# armstrap_eagle_1_0_0.net
KiCad netlist of a schematic drawn in EAGLE
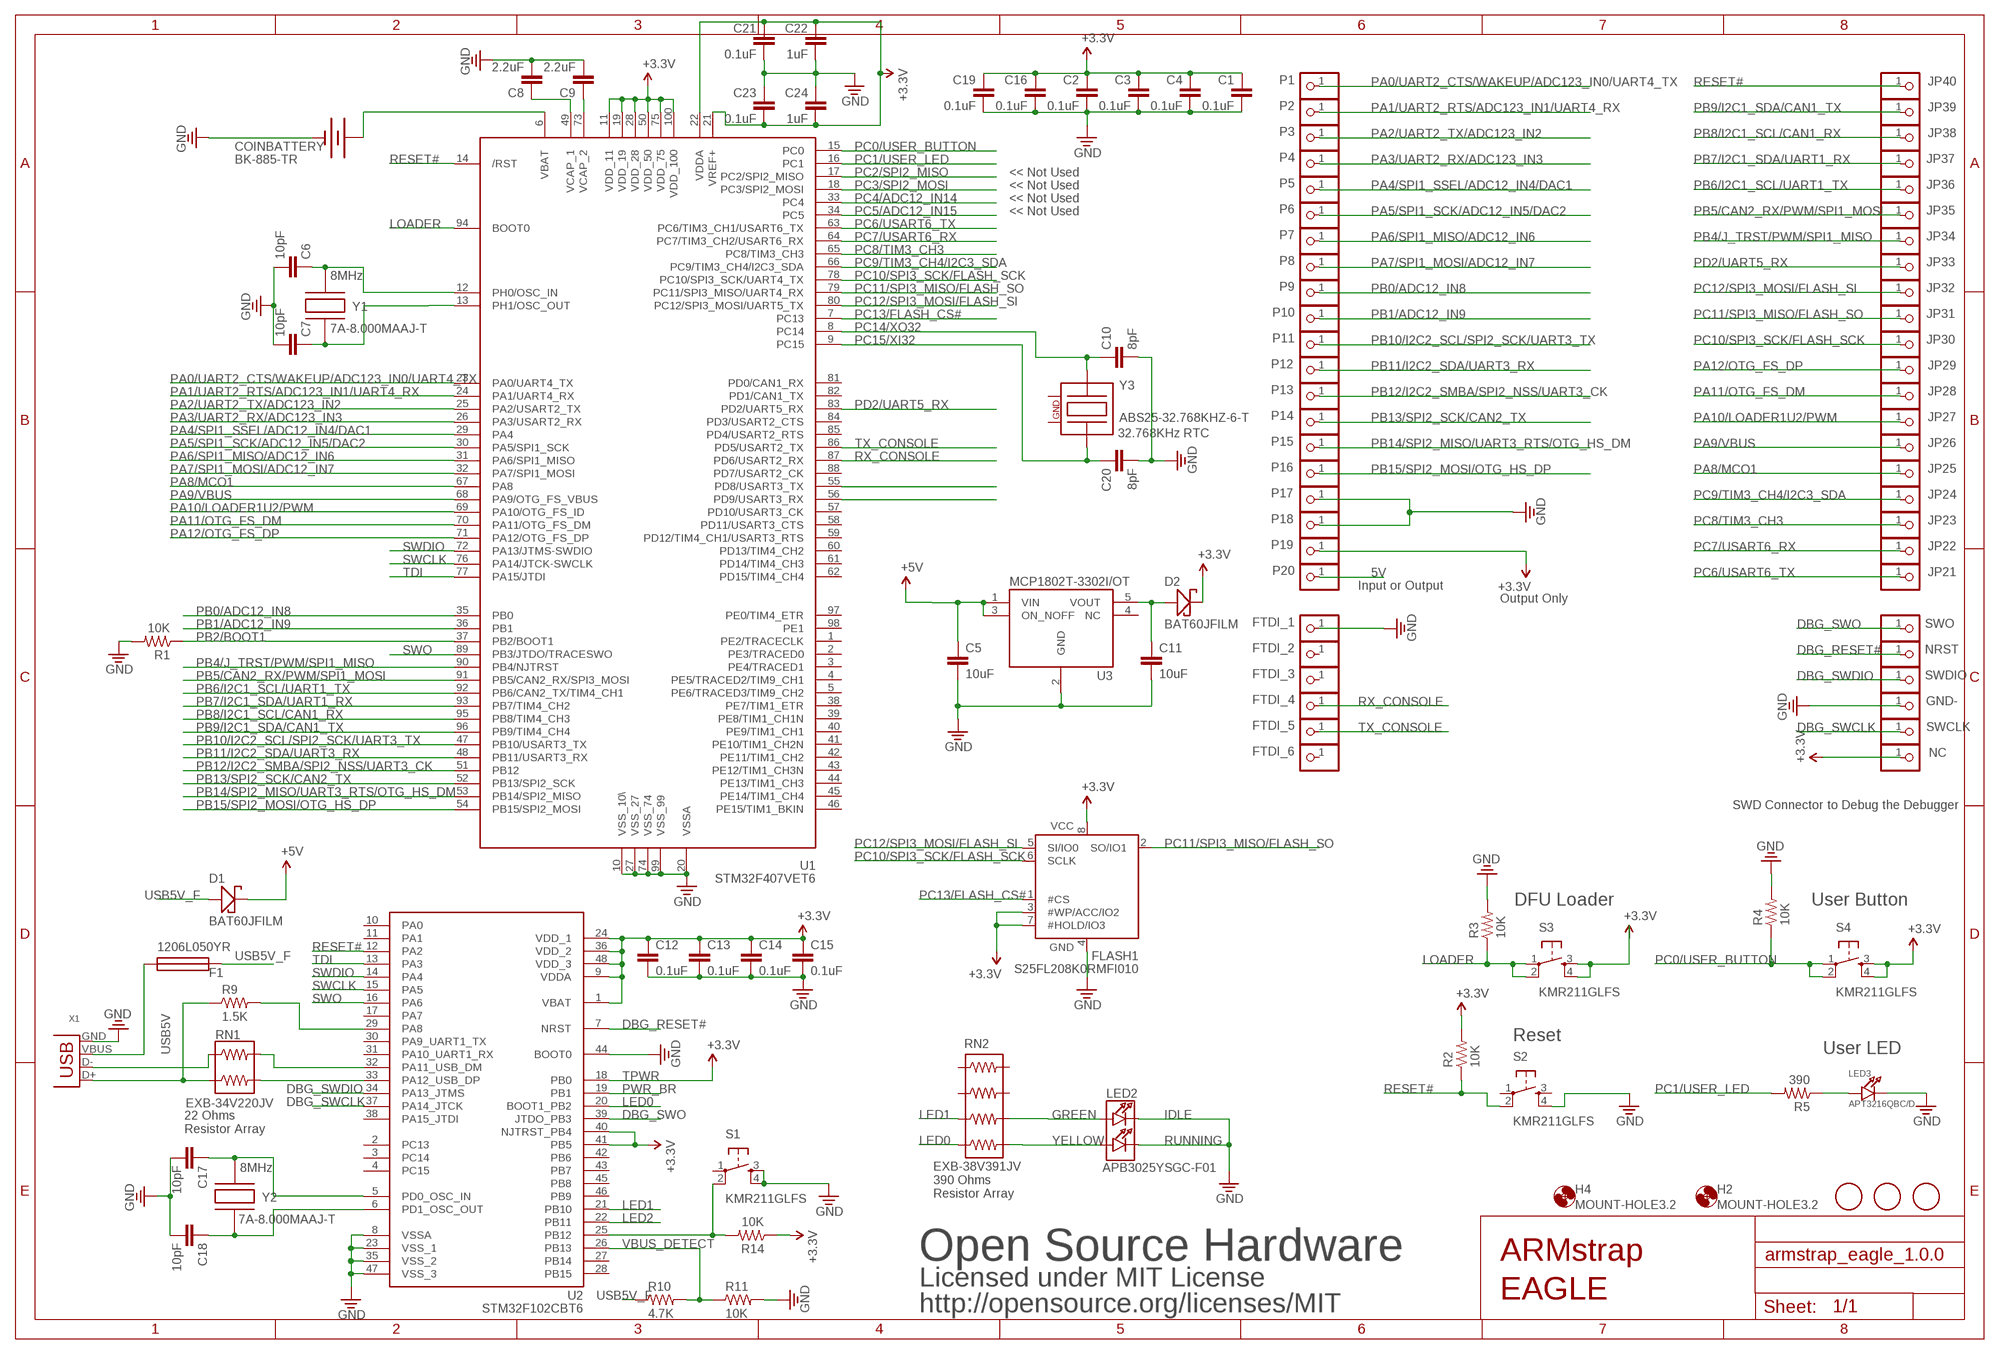
[diagram p0: schematic, sheet 1]

(export (version "E")
  (design (tool "Eeschema 10.0.6"))
  (components
    (comp (ref "C1")
      (value "0.1uF")
      (footprint "eagle-import:0805")
      (libsource (lib "eagle-import") (part "CAP0805"))
    )
    (comp (ref "C2")
      (value "0.1uF")
      (footprint "eagle-import:0805")
      (libsource (lib "eagle-import") (part "CAP0805"))
    )
    (comp (ref "C3")
      (value "0.1uF")
      (footprint "eagle-import:0805")
      (libsource (lib "eagle-import") (part "CAP0805"))
    )
    (comp (ref "C4")
      (value "0.1uF")
      (footprint "eagle-import:0805")
      (libsource (lib "eagle-import") (part "CAP0805"))
    )
    (comp (ref "C5")
      (value "10uF")
      (footprint "eagle-import:0805")
      (libsource (lib "eagle-import") (part "CAP0805"))
    )
    (comp (ref "C6")
      (value "10pF")
      (footprint "eagle-import:0805")
      (libsource (lib "eagle-import") (part "CAP0805"))
    )
    (comp (ref "C7")
      (value "10pF")
      (footprint "eagle-import:0805")
      (libsource (lib "eagle-import") (part "CAP0805"))
    )
    (comp (ref "C8")
      (value "2.2uF")
      (footprint "eagle-import:0805")
      (libsource (lib "eagle-import") (part "CAP0805"))
    )
    (comp (ref "C9")
      (value "2.2uF")
      (footprint "eagle-import:0805")
      (libsource (lib "eagle-import") (part "CAP0805"))
    )
    (comp (ref "C10")
      (value "8pF")
      (footprint "eagle-import:0805")
      (libsource (lib "eagle-import") (part "CAP0805"))
    )
    (comp (ref "C11")
      (value "10uF")
      (footprint "eagle-import:0805")
      (libsource (lib "eagle-import") (part "CAP0805"))
    )
    (comp (ref "C12")
      (value "0.1uF")
      (footprint "eagle-import:0805")
      (libsource (lib "eagle-import") (part "CAP0805"))
    )
    (comp (ref "C13")
      (value "0.1uF")
      (footprint "eagle-import:0805")
      (libsource (lib "eagle-import") (part "CAP0805"))
    )
    (comp (ref "C14")
      (value "0.1uF")
      (footprint "eagle-import:0805")
      (libsource (lib "eagle-import") (part "CAP0805"))
    )
    (comp (ref "C15")
      (value "0.1uF")
      (footprint "eagle-import:0805")
      (libsource (lib "eagle-import") (part "CAP0805"))
    )
    (comp (ref "C16")
      (value "0.1uF")
      (footprint "eagle-import:0805")
      (libsource (lib "eagle-import") (part "CAP0805"))
    )
    (comp (ref "C17")
      (value "10pF")
      (footprint "eagle-import:0805")
      (libsource (lib "eagle-import") (part "CAP0805"))
    )
    (comp (ref "C18")
      (value "10pF")
      (footprint "eagle-import:0805")
      (libsource (lib "eagle-import") (part "CAP0805"))
    )
    (comp (ref "C19")
      (value "0.1uF")
      (footprint "eagle-import:0805")
      (libsource (lib "eagle-import") (part "CAP0805"))
    )
    (comp (ref "C20")
      (value "8pF")
      (footprint "eagle-import:0805")
      (libsource (lib "eagle-import") (part "CAP0805"))
    )
    (comp (ref "C21")
      (value "0.1uF")
      (footprint "eagle-import:0805")
      (libsource (lib "eagle-import") (part "CAP0805"))
    )
    (comp (ref "C22")
      (value "1uF")
      (footprint "eagle-import:0805")
      (libsource (lib "eagle-import") (part "CAP0805"))
    )
    (comp (ref "C23")
      (value "0.1uF")
      (footprint "eagle-import:0805")
      (libsource (lib "eagle-import") (part "CAP0805"))
    )
    (comp (ref "C24")
      (value "1uF")
      (footprint "eagle-import:0805")
      (libsource (lib "eagle-import") (part "CAP0805"))
    )
    (comp (ref "COINBATTERY")
      (value "BK-885-TR")
      (footprint "eagle-import:BATTCON_12MM")
      (libsource (lib "eagle-import") (part "BATTERY12MM"))
    )
    (comp (ref "D1")
      (value "BAT60JFILM")
      (footprint "eagle-import:SOD-323")
      (libsource (lib "eagle-import") (part "SCHOTTKY"))
    )
    (comp (ref "D2")
      (value "BAT60JFILM")
      (footprint "eagle-import:SOD-323")
      (libsource (lib "eagle-import") (part "SCHOTTKY"))
    )
    (comp (ref "F1")
      (value "1206L050YR")
      (footprint "eagle-import:PTC-1206")
      (libsource (lib "eagle-import") (part "FUSE_PTC"))
    )
    (comp (ref "FID2")
      (value "FIDUCIAL")
      (footprint "eagle-import:FIDUCIAL_1MM")
      (libsource (lib "eagle-import") (part "FIDUCIAL"))
    )
    (comp (ref "FID3")
      (value "FIDUCIAL")
      (footprint "eagle-import:FIDUCIAL_1MM")
      (libsource (lib "eagle-import") (part "FIDUCIAL"))
    )
    (comp (ref "FID4")
      (value "FIDUCIAL")
      (footprint "eagle-import:FIDUCIAL_1MM")
      (libsource (lib "eagle-import") (part "FIDUCIAL"))
    )
    (comp (ref "FLASH1")
      (value "S25FL208K0RMFI010")
      (footprint "eagle-import:SOIC-8-WIDE")
      (libsource (lib "eagle-import") (part "FLASH-SPI"))
    )
    (comp (ref "FTDI_1")
      (value "PINHD-1X1")
      (footprint "eagle-import:1X01")
      (libsource (lib "eagle-import") (part "PINHD-1X1"))
    )
    (comp (ref "FTDI_2")
      (value "PINHD-1X1")
      (footprint "eagle-import:1X01")
      (libsource (lib "eagle-import") (part "PINHD-1X1"))
    )
    (comp (ref "FTDI_3")
      (value "PINHD-1X1")
      (footprint "eagle-import:1X01")
      (libsource (lib "eagle-import") (part "PINHD-1X1"))
    )
    (comp (ref "FTDI_4")
      (value "PINHD-1X1")
      (footprint "eagle-import:1X01")
      (libsource (lib "eagle-import") (part "PINHD-1X1"))
    )
    (comp (ref "FTDI_5")
      (value "PINHD-1X1")
      (footprint "eagle-import:1X01")
      (libsource (lib "eagle-import") (part "PINHD-1X1"))
    )
    (comp (ref "FTDI_6")
      (value "PINHD-1X1")
      (footprint "eagle-import:1X01")
      (libsource (lib "eagle-import") (part "PINHD-1X1"))
    )
    (comp (ref "GND-")
      (value "PINHD-1X1")
      (footprint "eagle-import:1X01")
      (libsource (lib "eagle-import") (part "PINHD-1X1"))
    )
    (comp (ref "H2")
      (value "MOUNT-HOLE3.2")
      (footprint "eagle-import:3,2")
      (libsource (lib "eagle-import") (part "MOUNT-HOLE3.2"))
    )
    (comp (ref "H4")
      (value "MOUNT-HOLE3.2")
      (footprint "eagle-import:3,2")
      (libsource (lib "eagle-import") (part "MOUNT-HOLE3.2"))
    )
    (comp (ref "JP21")
      (value "PINHD-1X1")
      (footprint "eagle-import:1X01")
      (libsource (lib "eagle-import") (part "PINHD-1X1"))
    )
    (comp (ref "JP22")
      (value "PINHD-1X1")
      (footprint "eagle-import:1X01")
      (libsource (lib "eagle-import") (part "PINHD-1X1"))
    )
    (comp (ref "JP23")
      (value "PINHD-1X1")
      (footprint "eagle-import:1X01")
      (libsource (lib "eagle-import") (part "PINHD-1X1"))
    )
    (comp (ref "JP24")
      (value "PINHD-1X1")
      (footprint "eagle-import:1X01")
      (libsource (lib "eagle-import") (part "PINHD-1X1"))
    )
    (comp (ref "JP25")
      (value "PINHD-1X1")
      (footprint "eagle-import:1X01")
      (libsource (lib "eagle-import") (part "PINHD-1X1"))
    )
    (comp (ref "JP26")
      (value "PINHD-1X1")
      (footprint "eagle-import:1X01")
      (libsource (lib "eagle-import") (part "PINHD-1X1"))
    )
    (comp (ref "JP27")
      (value "PINHD-1X1")
      (footprint "eagle-import:1X01")
      (libsource (lib "eagle-import") (part "PINHD-1X1"))
    )
    (comp (ref "JP28")
      (value "PINHD-1X1")
      (footprint "eagle-import:1X01")
      (libsource (lib "eagle-import") (part "PINHD-1X1"))
    )
    (comp (ref "JP29")
      (value "PINHD-1X1")
      (footprint "eagle-import:1X01")
      (libsource (lib "eagle-import") (part "PINHD-1X1"))
    )
    (comp (ref "JP30")
      (value "PINHD-1X1")
      (footprint "eagle-import:1X01")
      (libsource (lib "eagle-import") (part "PINHD-1X1"))
    )
    (comp (ref "JP31")
      (value "PINHD-1X1")
      (footprint "eagle-import:1X01")
      (libsource (lib "eagle-import") (part "PINHD-1X1"))
    )
    (comp (ref "JP32")
      (value "PINHD-1X1")
      (footprint "eagle-import:1X01")
      (libsource (lib "eagle-import") (part "PINHD-1X1"))
    )
    (comp (ref "JP33")
      (value "PINHD-1X1")
      (footprint "eagle-import:1X01")
      (libsource (lib "eagle-import") (part "PINHD-1X1"))
    )
    (comp (ref "JP34")
      (value "PINHD-1X1")
      (footprint "eagle-import:1X01")
      (libsource (lib "eagle-import") (part "PINHD-1X1"))
    )
    (comp (ref "JP35")
      (value "PINHD-1X1")
      (footprint "eagle-import:1X01")
      (libsource (lib "eagle-import") (part "PINHD-1X1"))
    )
    (comp (ref "JP36")
      (value "PINHD-1X1")
      (footprint "eagle-import:1X01")
      (libsource (lib "eagle-import") (part "PINHD-1X1"))
    )
    (comp (ref "JP37")
      (value "PINHD-1X1")
      (footprint "eagle-import:1X01")
      (libsource (lib "eagle-import") (part "PINHD-1X1"))
    )
    (comp (ref "JP38")
      (value "PINHD-1X1")
      (footprint "eagle-import:1X01")
      (libsource (lib "eagle-import") (part "PINHD-1X1"))
    )
    (comp (ref "JP39")
      (value "PINHD-1X1")
      (footprint "eagle-import:1X01")
      (libsource (lib "eagle-import") (part "PINHD-1X1"))
    )
    (comp (ref "JP40")
      (value "PINHD-1X1")
      (footprint "eagle-import:1X01")
      (libsource (lib "eagle-import") (part "PINHD-1X1"))
    )
    (comp (ref "LED2")
      (value "APB3025YSGC-F01")
      (footprint "eagle-import:CHIPLED_1206-DUAL")
      (libsource (lib "eagle-import") (part "LED-2"))
    )
    (comp (ref "LED3")
      (value "APT3216QBC/D")
      (footprint "eagle-import:CHIPLED_1206")
      (libsource (lib "eagle-import") (part "LED1206"))
    )
    (comp (ref "NC")
      (value "PINHD-1X1")
      (footprint "eagle-import:1X01")
      (libsource (lib "eagle-import") (part "PINHD-1X1"))
    )
    (comp (ref "NRST")
      (value "PINHD-1X1")
      (footprint "eagle-import:1X01")
      (libsource (lib "eagle-import") (part "PINHD-1X1"))
    )
    (comp (ref "P1")
      (value "PINHD-1X1")
      (footprint "eagle-import:1X01")
      (libsource (lib "eagle-import") (part "PINHD-1X1"))
    )
    (comp (ref "P2")
      (value "PINHD-1X1")
      (footprint "eagle-import:1X01")
      (libsource (lib "eagle-import") (part "PINHD-1X1"))
    )
    (comp (ref "P3")
      (value "PINHD-1X1")
      (footprint "eagle-import:1X01")
      (libsource (lib "eagle-import") (part "PINHD-1X1"))
    )
    (comp (ref "P4")
      (value "PINHD-1X1")
      (footprint "eagle-import:1X01")
      (libsource (lib "eagle-import") (part "PINHD-1X1"))
    )
    (comp (ref "P5")
      (value "PINHD-1X1")
      (footprint "eagle-import:1X01")
      (libsource (lib "eagle-import") (part "PINHD-1X1"))
    )
    (comp (ref "P6")
      (value "PINHD-1X1")
      (footprint "eagle-import:1X01")
      (libsource (lib "eagle-import") (part "PINHD-1X1"))
    )
    (comp (ref "P7")
      (value "PINHD-1X1")
      (footprint "eagle-import:1X01")
      (libsource (lib "eagle-import") (part "PINHD-1X1"))
    )
    (comp (ref "P8")
      (value "PINHD-1X1")
      (footprint "eagle-import:1X01")
      (libsource (lib "eagle-import") (part "PINHD-1X1"))
    )
    (comp (ref "P9")
      (value "PINHD-1X1")
      (footprint "eagle-import:1X01")
      (libsource (lib "eagle-import") (part "PINHD-1X1"))
    )
    (comp (ref "P10")
      (value "PINHD-1X1")
      (footprint "eagle-import:1X01")
      (libsource (lib "eagle-import") (part "PINHD-1X1"))
    )
    (comp (ref "P11")
      (value "PINHD-1X1")
      (footprint "eagle-import:1X01")
      (libsource (lib "eagle-import") (part "PINHD-1X1"))
    )
    (comp (ref "P12")
      (value "PINHD-1X1")
      (footprint "eagle-import:1X01")
      (libsource (lib "eagle-import") (part "PINHD-1X1"))
    )
    (comp (ref "P13")
      (value "PINHD-1X1")
      (footprint "eagle-import:1X01")
      (libsource (lib "eagle-import") (part "PINHD-1X1"))
    )
    (comp (ref "P14")
      (value "PINHD-1X1")
      (footprint "eagle-import:1X01")
      (libsource (lib "eagle-import") (part "PINHD-1X1"))
    )
    (comp (ref "P15")
      (value "PINHD-1X1")
      (footprint "eagle-import:1X01")
      (libsource (lib "eagle-import") (part "PINHD-1X1"))
    )
    (comp (ref "P16")
      (value "PINHD-1X1")
      (footprint "eagle-import:1X01")
      (libsource (lib "eagle-import") (part "PINHD-1X1"))
    )
    (comp (ref "P17")
      (value "PINHD-1X1")
      (footprint "eagle-import:1X01")
      (libsource (lib "eagle-import") (part "PINHD-1X1"))
    )
    (comp (ref "P18")
      (value "PINHD-1X1")
      (footprint "eagle-import:1X01")
      (libsource (lib "eagle-import") (part "PINHD-1X1"))
    )
    (comp (ref "P19")
      (value "PINHD-1X1")
      (footprint "eagle-import:1X01")
      (libsource (lib "eagle-import") (part "PINHD-1X1"))
    )
    (comp (ref "P20")
      (value "PINHD-1X1")
      (footprint "eagle-import:1X01")
      (libsource (lib "eagle-import") (part "PINHD-1X1"))
    )
    (comp (ref "R1")
      (value "10K")
      (footprint "eagle-import:0805")
      (libsource (lib "eagle-import") (part "RES0805"))
    )
    (comp (ref "R2")
      (value "10K")
      (footprint "eagle-import:0805")
      (libsource (lib "eagle-import") (part "RES0805"))
    )
    (comp (ref "R3")
      (value "10K")
      (footprint "eagle-import:0805")
      (libsource (lib "eagle-import") (part "RES0805"))
    )
    (comp (ref "R4")
      (value "10K")
      (footprint "eagle-import:0805")
      (libsource (lib "eagle-import") (part "RES0805"))
    )
    (comp (ref "R5")
      (value "390")
      (footprint "eagle-import:0805")
      (libsource (lib "eagle-import") (part "RES0805"))
    )
    (comp (ref "R9")
      (value "1.5K")
      (footprint "eagle-import:0805")
      (libsource (lib "eagle-import") (part "RES0805"))
    )
    (comp (ref "R10")
      (value "4.7K")
      (footprint "eagle-import:0805")
      (libsource (lib "eagle-import") (part "RES0805"))
    )
    (comp (ref "R11")
      (value "10K")
      (footprint "eagle-import:0805")
      (libsource (lib "eagle-import") (part "RES0805"))
    )
    (comp (ref "R14")
      (value "10K")
      (footprint "eagle-import:0805")
      (libsource (lib "eagle-import") (part "RES0805"))
    )
    (comp (ref "RN1")
      (value "EXB-34V220JV")
      (footprint "eagle-import:0603-ARC2")
      (libsource (lib "eagle-import") (part "RES-2"))
    )
    (comp (ref "RN2")
      (value "EXB-38V391JV")
      (footprint "eagle-import:0603-ARC4")
      (libsource (lib "eagle-import") (part "RES-4"))
    )
    (comp (ref "S1")
      (value "KMR211GLFS")
      (footprint "eagle-import:KMR_SWITCH")
      (libsource (lib "eagle-import") (part "TAC_SWITCH"))
    )
    (comp (ref "S2")
      (value "KMR211GLFS")
      (footprint "eagle-import:KMR_SWITCH")
      (libsource (lib "eagle-import") (part "TAC_SWITCH"))
    )
    (comp (ref "S3")
      (value "KMR211GLFS")
      (footprint "eagle-import:KMR_SWITCH")
      (libsource (lib "eagle-import") (part "TAC_SWITCH"))
    )
    (comp (ref "S4")
      (value "KMR211GLFS")
      (footprint "eagle-import:KMR_SWITCH")
      (libsource (lib "eagle-import") (part "TAC_SWITCH"))
    )
    (comp (ref "SWCLK")
      (value "PINHD-1X1")
      (footprint "eagle-import:1X01")
      (libsource (lib "eagle-import") (part "PINHD-1X1"))
    )
    (comp (ref "SWDIO")
      (value "PINHD-1X1")
      (footprint "eagle-import:1X01")
      (libsource (lib "eagle-import") (part "PINHD-1X1"))
    )
    (comp (ref "SWO")
      (value "PINHD-1X1")
      (footprint "eagle-import:1X01")
      (libsource (lib "eagle-import") (part "PINHD-1X1"))
    )
    (comp (ref "U1")
      (value "STM32F407VET6")
      (footprint "eagle-import:LQFP100")
      (libsource (lib "eagle-import") (part "STM32F407VET6"))
    )
    (comp (ref "U2")
      (value "STM32F102CBT6")
      (footprint "eagle-import:LQFP48")
      (libsource (lib "eagle-import") (part "STM32F102CBT6"))
    )
    (comp (ref "U3")
      (value "MCP1802T-3302I/OT")
      (footprint "eagle-import:MCP1802-SOT23")
      (libsource (lib "eagle-import") (part "MCP1802"))
    )
    (comp (ref "X1")
      (value "10033526-N3212MLF")
      (footprint "eagle-import:USB-MB-S")
      (libsource (lib "eagle-import") (part "USB-MB-S"))
    )
    (comp (ref "Y1")
      (value "7A-8.000MAAJ-T")
      (footprint "eagle-import:CRYSTAL-SMD-5.0MM-3.2MM-2")
      (libsource (lib "eagle-import") (part "CRYSTAL-2"))
    )
    (comp (ref "Y2")
      (value "7A-8.000MAAJ-T")
      (footprint "eagle-import:CRYSTAL-SMD-5.0MM-3.2MM-2")
      (libsource (lib "eagle-import") (part "CRYSTAL-2"))
    )
    (comp (ref "Y3")
      (value "ABS25-32.768KHZ-6-T")
      (footprint "eagle-import:CRYSTAL-SMD-32.768KHZ")
      (libsource (lib "eagle-import") (part "CRYSTAL"))
    )
  )
  (nets
    (net (code "1") (name "+3.3V") (class "Default")
      (node (ref "C1") (pin "1") (pinfunction "1_1") (pintype "passive"))
      (node (ref "C12") (pin "1") (pinfunction "1_1") (pintype "passive"))
      (node (ref "C13") (pin "1") (pinfunction "1_1") (pintype "passive"))
      (node (ref "C14") (pin "1") (pinfunction "1_1") (pintype "passive"))
      (node (ref "C15") (pin "1") (pinfunction "1_1") (pintype "passive"))
      (node (ref "C16") (pin "1") (pinfunction "1_1") (pintype "passive"))
      (node (ref "C19") (pin "1") (pinfunction "1_1") (pintype "passive"))
      (node (ref "C2") (pin "1") (pinfunction "1_1") (pintype "passive"))
      (node (ref "C21") (pin "1") (pinfunction "1_1") (pintype "passive"))
      (node (ref "C22") (pin "1") (pinfunction "1_1") (pintype "passive"))
      (node (ref "C23") (pin "2") (pinfunction "2_2") (pintype "passive"))
      (node (ref "C24") (pin "2") (pinfunction "2_2") (pintype "passive"))
      (node (ref "C3") (pin "1") (pinfunction "1_1") (pintype "passive"))
      (node (ref "C4") (pin "1") (pinfunction "1_1") (pintype "passive"))
      (node (ref "D2") (pin "CATHODE") (pinfunction "C_CATHODE") (pintype "power_in"))
      (node (ref "FLASH1") (pin "3") (pinfunction "#WP/ACC/IO2_3") (pintype "bidirectional"))
      (node (ref "FLASH1") (pin "7") (pinfunction "#HOLD/IO3_7") (pintype "bidirectional"))
      (node (ref "FLASH1") (pin "8") (pinfunction "VCC_8") (pintype "power_in"))
      (node (ref "NC") (pin "1") (pinfunction "1_1") (pintype "passive"))
      (node (ref "P19") (pin "1") (pinfunction "1_1") (pintype "passive"))
      (node (ref "R14") (pin "1") (pinfunction "1_1") (pintype "passive"))
      (node (ref "R2") (pin "2") (pinfunction "2_2") (pintype "passive"))
      (node (ref "S3") (pin "3") (pinfunction "3_3") (pintype "passive"))
      (node (ref "S3") (pin "4") (pinfunction "4_4") (pintype "passive"))
      (node (ref "S4") (pin "3") (pinfunction "3_3") (pintype "passive"))
      (node (ref "S4") (pin "4") (pinfunction "4_4") (pintype "passive"))
      (node (ref "U1") (pin "100") (pinfunction "VDD_100_100") (pintype "power_in"))
      (node (ref "U1") (pin "11") (pinfunction "VDD_11_11") (pintype "power_in"))
      (node (ref "U1") (pin "19") (pinfunction "VDD_19_19") (pintype "power_in"))
      (node (ref "U1") (pin "21") (pinfunction "VREF+_21") (pintype "power_in"))
      (node (ref "U1") (pin "22") (pinfunction "VDDA_22") (pintype "power_in"))
      (node (ref "U1") (pin "28") (pinfunction "VDD_28_28") (pintype "power_in"))
      (node (ref "U1") (pin "50") (pinfunction "VDD_50_50") (pintype "power_in"))
      (node (ref "U1") (pin "75") (pinfunction "VDD_75_75") (pintype "power_in"))
      (node (ref "U2") (pin "1") (pinfunction "VBAT_1") (pintype "power_in"))
      (node (ref "U2") (pin "18") (pinfunction "PB0_18") (pintype "bidirectional"))
      (node (ref "U2") (pin "24") (pinfunction "VDD_1_24") (pintype "power_in"))
      (node (ref "U2") (pin "36") (pinfunction "VDD_2_36") (pintype "power_in"))
      (node (ref "U2") (pin "40") (pinfunction "NJTRST_PB4_40") (pintype "bidirectional"))
      (node (ref "U2") (pin "41") (pinfunction "PB5_41") (pintype "bidirectional"))
      (node (ref "U2") (pin "48") (pinfunction "VDD_3_48") (pintype "power_in"))
      (node (ref "U2") (pin "9") (pinfunction "VDDA_9") (pintype "power_in"))
    )
    (net (code "2") (name "+5V") (class "Default")
      (node (ref "C5") (pin "1") (pinfunction "1_1") (pintype "passive"))
      (node (ref "D1") (pin "CATHODE") (pinfunction "C_CATHODE") (pintype "power_in"))
      (node (ref "P20") (pin "1") (pinfunction "1_1") (pintype "passive"))
      (node (ref "U3") (pin "1") (pinfunction "VIN_1") (pintype "power_in"))
      (node (ref "U3") (pin "3") (pinfunction "ON_NOFF_3") (pintype "bidirectional"))
    )
    (net (code "3") (name "/2") (class "Default")
      (node (ref "Y3") (pin "2") (pinfunction "2_2") (pintype "power_in"))
    )
    (net (code "4") (name "/4") (class "Default")
      (node (ref "Y3") (pin "3") (pinfunction "4_3") (pintype "power_in"))
    )
    (net (code "5") (name "/DBG_RESET#") (class "Default")
      (node (ref "NRST") (pin "1") (pinfunction "1_1") (pintype "passive"))
      (node (ref "U2") (pin "7") (pinfunction "NRST_7") (pintype "bidirectional"))
    )
    (net (code "6") (name "/DBG_SWCLK") (class "Default")
      (node (ref "SWCLK") (pin "1") (pinfunction "1_1") (pintype "passive"))
      (node (ref "U2") (pin "37") (pinfunction "PA14_JTCK_37") (pintype "bidirectional"))
    )
    (net (code "7") (name "/DBG_SWDIO") (class "Default")
      (node (ref "SWDIO") (pin "1") (pinfunction "1_1") (pintype "passive"))
      (node (ref "U2") (pin "34") (pinfunction "PA13_JTMS_34") (pintype "bidirectional"))
    )
    (net (code "8") (name "/DBG_SWO") (class "Default")
      (node (ref "SWO") (pin "1") (pinfunction "1_1") (pintype "passive"))
      (node (ref "U2") (pin "39") (pinfunction "JTDO_PB3_39") (pintype "bidirectional"))
    )
    (net (code "9") (name "/LED0") (class "Default")
      (node (ref "RN2") (pin "4") (pinfunction "4_4") (pintype "passive"))
      (node (ref "U2") (pin "20") (pinfunction "BOOT1_PB2_20") (pintype "bidirectional"))
    )
    (net (code "10") (name "/LED1") (class "Default")
      (node (ref "RN2") (pin "3") (pinfunction "3_3") (pintype "passive"))
      (node (ref "U2") (pin "21") (pinfunction "PB10_21") (pintype "bidirectional"))
    )
    (net (code "11") (name "/LED2") (class "Default")
      (node (ref "U2") (pin "22") (pinfunction "PB11_22") (pintype "bidirectional"))
    )
    (net (code "12") (name "/LOADER") (class "Default")
      (node (ref "R3") (pin "1") (pinfunction "1_1") (pintype "passive"))
      (node (ref "S3") (pin "1") (pinfunction "1_1") (pintype "passive"))
      (node (ref "S3") (pin "2") (pinfunction "2_2") (pintype "passive"))
      (node (ref "U1") (pin "94") (pinfunction "BOOT0_94") (pintype "bidirectional"))
    )
    (net (code "13") (name "/PA0{slash}UART2_CTS{slash}WAKEUP{slash}ADC123_IN0{slash}UART4_TX") (class "Default")
      (node (ref "P1") (pin "1") (pinfunction "1_1") (pintype "passive"))
      (node (ref "U1") (pin "23") (pinfunction "PA0/UART4_TX_23") (pintype "bidirectional"))
    )
    (net (code "14") (name "/PA1{slash}UART2_RTS{slash}ADC123_IN1{slash}UART4_RX") (class "Default")
      (node (ref "P2") (pin "1") (pinfunction "1_1") (pintype "passive"))
      (node (ref "U1") (pin "24") (pinfunction "PA1/UART4_RX_24") (pintype "bidirectional"))
    )
    (net (code "15") (name "/PA2{slash}UART2_TX{slash}ADC123_IN2") (class "Default")
      (node (ref "P3") (pin "1") (pinfunction "1_1") (pintype "passive"))
      (node (ref "U1") (pin "25") (pinfunction "PA2/USART2_TX_25") (pintype "bidirectional"))
    )
    (net (code "16") (name "/PA3{slash}UART2_RX{slash}ADC123_IN3") (class "Default")
      (node (ref "P4") (pin "1") (pinfunction "1_1") (pintype "passive"))
      (node (ref "U1") (pin "26") (pinfunction "PA3/USART2_RX_26") (pintype "bidirectional"))
    )
    (net (code "17") (name "/PA4{slash}SPI1_SSEL{slash}ADC12_IN4{slash}DAC1") (class "Default")
      (node (ref "P5") (pin "1") (pinfunction "1_1") (pintype "passive"))
      (node (ref "U1") (pin "29") (pinfunction "PA4_29") (pintype "bidirectional"))
    )
    (net (code "18") (name "/PA5{slash}SPI1_SCK{slash}ADC12_IN5{slash}DAC2") (class "Default")
      (node (ref "P6") (pin "1") (pinfunction "1_1") (pintype "passive"))
      (node (ref "U1") (pin "30") (pinfunction "PA5/SPI1_SCK_30") (pintype "bidirectional"))
    )
    (net (code "19") (name "/PA6{slash}SPI1_MISO{slash}ADC12_IN6") (class "Default")
      (node (ref "P7") (pin "1") (pinfunction "1_1") (pintype "passive"))
      (node (ref "U1") (pin "31") (pinfunction "PA6/SPI1_MISO_31") (pintype "bidirectional"))
    )
    (net (code "20") (name "/PA7{slash}SPI1_MOSI{slash}ADC12_IN7") (class "Default")
      (node (ref "P8") (pin "1") (pinfunction "1_1") (pintype "passive"))
      (node (ref "U1") (pin "32") (pinfunction "PA7/SPI1_MOSI_32") (pintype "bidirectional"))
    )
    (net (code "21") (name "/PA8{slash}MCO1") (class "Default")
      (node (ref "JP25") (pin "1") (pinfunction "1_1") (pintype "passive"))
      (node (ref "U1") (pin "67") (pinfunction "PA8_67") (pintype "bidirectional"))
    )
    (net (code "22") (name "/PA9{slash}VBUS") (class "Default")
      (node (ref "JP26") (pin "1") (pinfunction "1_1") (pintype "passive"))
      (node (ref "U1") (pin "68") (pinfunction "PA9/OTG_FS_VBUS_68") (pintype "bidirectional"))
    )
    (net (code "23") (name "/PA10{slash}LOADER1U2{slash}PWM") (class "Default")
      (node (ref "JP27") (pin "1") (pinfunction "1_1") (pintype "passive"))
      (node (ref "U1") (pin "69") (pinfunction "PA10/OTG_FS_ID_69") (pintype "bidirectional"))
    )
    (net (code "24") (name "/PA11{slash}OTG_FS_DM") (class "Default")
      (node (ref "JP28") (pin "1") (pinfunction "1_1") (pintype "passive"))
      (node (ref "U1") (pin "70") (pinfunction "PA11/OTG_FS_DM_70") (pintype "bidirectional"))
    )
    (net (code "25") (name "/PA12{slash}OTG_FS_DP") (class "Default")
      (node (ref "JP29") (pin "1") (pinfunction "1_1") (pintype "passive"))
      (node (ref "U1") (pin "71") (pinfunction "PA12/OTG_FS_DP_71") (pintype "bidirectional"))
    )
    (net (code "26") (name "/PB0{slash}ADC12_IN8") (class "Default")
      (node (ref "P9") (pin "1") (pinfunction "1_1") (pintype "passive"))
      (node (ref "U1") (pin "35") (pinfunction "PB0_35") (pintype "bidirectional"))
    )
    (net (code "27") (name "/PB1{slash}ADC12_IN9") (class "Default")
      (node (ref "P10") (pin "1") (pinfunction "1_1") (pintype "passive"))
      (node (ref "U1") (pin "36") (pinfunction "PB1_36") (pintype "bidirectional"))
    )
    (net (code "28") (name "/PB2{slash}BOOT1") (class "Default")
      (node (ref "R1") (pin "1") (pinfunction "1_1") (pintype "passive"))
      (node (ref "U1") (pin "37") (pinfunction "PB2/BOOT1_37") (pintype "bidirectional"))
    )
    (net (code "29") (name "/PB4{slash}J_TRST{slash}PWM{slash}SPI1_MISO") (class "Default")
      (node (ref "JP34") (pin "1") (pinfunction "1_1") (pintype "passive"))
      (node (ref "U1") (pin "90") (pinfunction "PB4/NJTRST_90") (pintype "bidirectional"))
    )
    (net (code "30") (name "/PB5{slash}CAN2_RX{slash}PWM{slash}SPI1_MOSI") (class "Default")
      (node (ref "JP35") (pin "1") (pinfunction "1_1") (pintype "passive"))
      (node (ref "U1") (pin "91") (pinfunction "PB5/CAN2_RX/SPI3_MOSI_91") (pintype "bidirectional"))
    )
    (net (code "31") (name "/PB6{slash}I2C1_SCL{slash}UART1_TX") (class "Default")
      (node (ref "JP36") (pin "1") (pinfunction "1_1") (pintype "passive"))
      (node (ref "U1") (pin "92") (pinfunction "PB6/CAN2_TX/TIM4_CH1_92") (pintype "bidirectional"))
    )
    (net (code "32") (name "/PB7{slash}I2C1_SDA{slash}UART1_RX") (class "Default")
      (node (ref "JP37") (pin "1") (pinfunction "1_1") (pintype "passive"))
      (node (ref "U1") (pin "93") (pinfunction "PB7/TIM4_CH2_93") (pintype "bidirectional"))
    )
    (net (code "33") (name "/PB8{slash}I2C1_SCL{slash}CAN1_RX") (class "Default")
      (node (ref "JP38") (pin "1") (pinfunction "1_1") (pintype "passive"))
      (node (ref "U1") (pin "95") (pinfunction "PB8/TIM4_CH3_95") (pintype "bidirectional"))
    )
    (net (code "34") (name "/PB9{slash}I2C1_SDA{slash}CAN1_TX") (class "Default")
      (node (ref "JP39") (pin "1") (pinfunction "1_1") (pintype "passive"))
      (node (ref "U1") (pin "96") (pinfunction "PB9/TIM4_CH4_96") (pintype "bidirectional"))
    )
    (net (code "35") (name "/PB10{slash}I2C2_SCL{slash}SPI2_SCK{slash}UART3_TX") (class "Default")
      (node (ref "P11") (pin "1") (pinfunction "1_1") (pintype "passive"))
      (node (ref "U1") (pin "47") (pinfunction "PB10/USART3_TX_47") (pintype "bidirectional"))
    )
    (net (code "36") (name "/PB11{slash}I2C2_SDA{slash}UART3_RX") (class "Default")
      (node (ref "P12") (pin "1") (pinfunction "1_1") (pintype "passive"))
      (node (ref "U1") (pin "48") (pinfunction "PB11/USART3_RX_48") (pintype "bidirectional"))
    )
    (net (code "37") (name "/PB12{slash}I2C2_SMBA{slash}SPI2_NSS{slash}UART3_CK") (class "Default")
      (node (ref "P13") (pin "1") (pinfunction "1_1") (pintype "passive"))
      (node (ref "U1") (pin "51") (pinfunction "PB12_51") (pintype "bidirectional"))
    )
    (net (code "38") (name "/PB13{slash}SPI2_SCK{slash}CAN2_TX") (class "Default")
      (node (ref "P14") (pin "1") (pinfunction "1_1") (pintype "passive"))
      (node (ref "U1") (pin "52") (pinfunction "PB13/SPI2_SCK_52") (pintype "bidirectional"))
    )
    (net (code "39") (name "/PB14{slash}SPI2_MISO{slash}UART3_RTS{slash}OTG_HS_DM") (class "Default")
      (node (ref "P15") (pin "1") (pinfunction "1_1") (pintype "passive"))
      (node (ref "U1") (pin "53") (pinfunction "PB14/SPI2_MISO_53") (pintype "bidirectional"))
    )
    (net (code "40") (name "/PB15{slash}SPI2_MOSI{slash}OTG_HS_DP") (class "Default")
      (node (ref "P16") (pin "1") (pinfunction "1_1") (pintype "passive"))
      (node (ref "U1") (pin "54") (pinfunction "PB15/SPI2_MOSI_54") (pintype "bidirectional"))
    )
    (net (code "41") (name "/PC0{slash}USER_BUTTON") (class "Default")
      (node (ref "R4") (pin "1") (pinfunction "1_1") (pintype "passive"))
      (node (ref "S4") (pin "1") (pinfunction "1_1") (pintype "passive"))
      (node (ref "S4") (pin "2") (pinfunction "2_2") (pintype "passive"))
      (node (ref "U1") (pin "15") (pinfunction "PC0_15") (pintype "bidirectional"))
    )
    (net (code "42") (name "/PC1{slash}USER_LED") (class "Default")
      (node (ref "R5") (pin "2") (pinfunction "2_2") (pintype "passive"))
      (node (ref "U1") (pin "16") (pinfunction "PC1_16") (pintype "bidirectional"))
    )
    (net (code "43") (name "/PC2{slash}SPI2_MISO") (class "Default")
      (node (ref "U1") (pin "17") (pinfunction "PC2/SPI2_MISO_17") (pintype "bidirectional"))
    )
    (net (code "44") (name "/PC3{slash}SPI2_MOSI") (class "Default")
      (node (ref "U1") (pin "18") (pinfunction "PC3/SPI2_MOSI_18") (pintype "bidirectional"))
    )
    (net (code "45") (name "/PC4{slash}ADC12_IN14") (class "Default")
      (node (ref "U1") (pin "33") (pinfunction "PC4_33") (pintype "bidirectional"))
    )
    (net (code "46") (name "/PC5{slash}ADC12_IN15") (class "Default")
      (node (ref "U1") (pin "34") (pinfunction "PC5_34") (pintype "bidirectional"))
    )
    (net (code "47") (name "/PC6{slash}USART6_TX") (class "Default")
      (node (ref "JP21") (pin "1") (pinfunction "1_1") (pintype "passive"))
      (node (ref "U1") (pin "63") (pinfunction "PC6/TIM3_CH1/USART6_TX_63") (pintype "bidirectional"))
    )
    (net (code "48") (name "/PC7{slash}USART6_RX") (class "Default")
      (node (ref "JP22") (pin "1") (pinfunction "1_1") (pintype "passive"))
      (node (ref "U1") (pin "64") (pinfunction "PC7/TIM3_CH2/USART6_RX_64") (pintype "bidirectional"))
    )
    (net (code "49") (name "/PC8{slash}TIM3_CH3") (class "Default")
      (node (ref "JP23") (pin "1") (pinfunction "1_1") (pintype "passive"))
      (node (ref "U1") (pin "65") (pinfunction "PC8/TIM3_CH3_65") (pintype "bidirectional"))
    )
    (net (code "50") (name "/PC9{slash}TIM3_CH4{slash}I2C3_SDA") (class "Default")
      (node (ref "JP24") (pin "1") (pinfunction "1_1") (pintype "passive"))
      (node (ref "U1") (pin "66") (pinfunction "PC9/TIM3_CH4/I2C3_SDA_66") (pintype "bidirectional"))
    )
    (net (code "51") (name "/PC10{slash}SPI3_SCK{slash}FLASH_SCK") (class "Default")
      (node (ref "FLASH1") (pin "6") (pinfunction "SCLK_6") (pintype "bidirectional"))
      (node (ref "JP30") (pin "1") (pinfunction "1_1") (pintype "passive"))
      (node (ref "U1") (pin "78") (pinfunction "PC10/SPI3_SCK/UART4_TX_78") (pintype "bidirectional"))
    )
    (net (code "52") (name "/PC11{slash}SPI3_MISO{slash}FLASH_SO") (class "Default")
      (node (ref "FLASH1") (pin "2") (pinfunction "SO/IO1_2") (pintype "bidirectional"))
      (node (ref "JP31") (pin "1") (pinfunction "1_1") (pintype "passive"))
      (node (ref "U1") (pin "79") (pinfunction "PC11/SPI3_MISO/UART4_RX_79") (pintype "bidirectional"))
    )
    (net (code "53") (name "/PC12{slash}SPI3_MOSI{slash}FLASH_SI") (class "Default")
      (node (ref "FLASH1") (pin "5") (pinfunction "SI/IO0_5") (pintype "bidirectional"))
      (node (ref "JP32") (pin "1") (pinfunction "1_1") (pintype "passive"))
      (node (ref "U1") (pin "80") (pinfunction "PC12/SPI3_MOSI/UART5_TX_80") (pintype "bidirectional"))
    )
    (net (code "54") (name "/PC13{slash}FLASH_CS#") (class "Default")
      (node (ref "FLASH1") (pin "1") (pinfunction "#CS_1") (pintype "bidirectional"))
      (node (ref "U1") (pin "7") (pinfunction "PC13_7") (pintype "bidirectional"))
    )
    (net (code "55") (name "/PC14{slash}XO32") (class "Default")
      (node (ref "C10") (pin "1") (pinfunction "1_1") (pintype "passive"))
      (node (ref "U1") (pin "8") (pinfunction "PC14_8") (pintype "bidirectional"))
      (node (ref "Y3") (pin "1") (pinfunction "1_1") (pintype "bidirectional"))
    )
    (net (code "56") (name "/PC15{slash}XI32") (class "Default")
      (node (ref "C20") (pin "1") (pinfunction "1_1") (pintype "passive"))
      (node (ref "U1") (pin "9") (pinfunction "PC15_9") (pintype "bidirectional"))
      (node (ref "Y3") (pin "4") (pinfunction "3_4") (pintype "bidirectional"))
    )
    (net (code "57") (name "/PD2{slash}UART5_RX") (class "Default")
      (node (ref "JP33") (pin "1") (pinfunction "1_1") (pintype "passive"))
      (node (ref "U1") (pin "83") (pinfunction "PD2/UART5_RX_83") (pintype "bidirectional"))
    )
    (net (code "58") (name "/PWR_BR") (class "Default")
      (node (ref "U2") (pin "19") (pinfunction "PB1_19") (pintype "bidirectional"))
    )
    (net (code "59") (name "/RESET#") (class "Default")
      (node (ref "JP40") (pin "1") (pinfunction "1_1") (pintype "passive"))
      (node (ref "R2") (pin "1") (pinfunction "1_1") (pintype "passive"))
      (node (ref "S2") (pin "2") (pinfunction "2_2") (pintype "passive"))
      (node (ref "U1") (pin "14") (pinfunction "/RST_14") (pintype "bidirectional"))
      (node (ref "U2") (pin "12") (pinfunction "PA2_12") (pintype "bidirectional"))
    )
    (net (code "60") (name "/RX_CONSOLE") (class "Default")
      (node (ref "FTDI_4") (pin "1") (pinfunction "1_1") (pintype "passive"))
      (node (ref "U1") (pin "87") (pinfunction "PD6/USART2_RX_87") (pintype "bidirectional"))
    )
    (net (code "61") (name "/SWCLK") (class "Default")
      (node (ref "U1") (pin "76") (pinfunction "PA14/JTCK-SWCLK_76") (pintype "bidirectional"))
      (node (ref "U2") (pin "15") (pinfunction "PA5_15") (pintype "bidirectional"))
    )
    (net (code "62") (name "/SWDIO") (class "Default")
      (node (ref "U1") (pin "72") (pinfunction "PA13/JTMS-SWDIO_72") (pintype "bidirectional"))
      (node (ref "U2") (pin "14") (pinfunction "PA4_14") (pintype "bidirectional"))
    )
    (net (code "63") (name "/SWO") (class "Default")
      (node (ref "U1") (pin "89") (pinfunction "PB3/JTDO/TRACESWO_89") (pintype "bidirectional"))
      (node (ref "U2") (pin "16") (pinfunction "PA6_16") (pintype "bidirectional"))
    )
    (net (code "64") (name "/TDI") (class "Default")
      (node (ref "U1") (pin "77") (pinfunction "PA15/JTDI_77") (pintype "bidirectional"))
      (node (ref "U2") (pin "13") (pinfunction "PA3_13") (pintype "bidirectional"))
    )
    (net (code "65") (name "/TX_CONSOLE") (class "Default")
      (node (ref "FTDI_5") (pin "1") (pinfunction "1_1") (pintype "passive"))
      (node (ref "U1") (pin "86") (pinfunction "PD5/USART2_TX_86") (pintype "bidirectional"))
    )
    (net (code "66") (name "/USB5V") (class "Default")
      (node (ref "F1") (pin "1") (pinfunction "1_1") (pintype "bidirectional"))
      (node (ref "X1") (pin "VBUS") (pinfunction "VBUS_VBUS") (pintype "bidirectional"))
    )
    (net (code "67") (name "/USB5V_F") (class "Default")
      (node (ref "D1") (pin "ANODE") (pinfunction "A_ANODE") (pintype "power_in"))
      (node (ref "F1") (pin "2") (pinfunction "2_2") (pintype "bidirectional"))
      (node (ref "R10") (pin "1") (pinfunction "1_1") (pintype "passive"))
    )
    (net (code "68") (name "/VBUS_DETECT") (class "Default")
      (node (ref "R10") (pin "2") (pinfunction "2_2") (pintype "passive"))
      (node (ref "R11") (pin "1") (pinfunction "1_1") (pintype "passive"))
      (node (ref "U2") (pin "26") (pinfunction "PB13_26") (pintype "bidirectional"))
    )
    (net (code "69") (name "GND") (class "Default")
      (node (ref "C1") (pin "2") (pinfunction "2_2") (pintype "passive"))
      (node (ref "C10") (pin "2") (pinfunction "2_2") (pintype "passive"))
      (node (ref "C11") (pin "2") (pinfunction "2_2") (pintype "passive"))
      (node (ref "C12") (pin "2") (pinfunction "2_2") (pintype "passive"))
      (node (ref "C13") (pin "2") (pinfunction "2_2") (pintype "passive"))
      (node (ref "C14") (pin "2") (pinfunction "2_2") (pintype "passive"))
      (node (ref "C15") (pin "2") (pinfunction "2_2") (pintype "passive"))
      (node (ref "C16") (pin "2") (pinfunction "2_2") (pintype "passive"))
      (node (ref "C17") (pin "2") (pinfunction "2_2") (pintype "passive"))
      (node (ref "C18") (pin "2") (pinfunction "2_2") (pintype "passive"))
      (node (ref "C19") (pin "2") (pinfunction "2_2") (pintype "passive"))
      (node (ref "C2") (pin "2") (pinfunction "2_2") (pintype "passive"))
      (node (ref "C20") (pin "2") (pinfunction "2_2") (pintype "passive"))
      (node (ref "C21") (pin "2") (pinfunction "2_2") (pintype "passive"))
      (node (ref "C22") (pin "2") (pinfunction "2_2") (pintype "passive"))
      (node (ref "C23") (pin "1") (pinfunction "1_1") (pintype "passive"))
      (node (ref "C24") (pin "1") (pinfunction "1_1") (pintype "passive"))
      (node (ref "C3") (pin "2") (pinfunction "2_2") (pintype "passive"))
      (node (ref "C4") (pin "2") (pinfunction "2_2") (pintype "passive"))
      (node (ref "C5") (pin "2") (pinfunction "2_2") (pintype "passive"))
      (node (ref "C6") (pin "2") (pinfunction "2_2") (pintype "passive"))
      (node (ref "C7") (pin "2") (pinfunction "2_2") (pintype "passive"))
      (node (ref "C8") (pin "2") (pinfunction "2_2") (pintype "passive"))
      (node (ref "C9") (pin "2") (pinfunction "2_2") (pintype "passive"))
      (node (ref "COINBATTERY") (pin "GND") (pinfunction "-_GND") (pintype "power_in"))
      (node (ref "FLASH1") (pin "4") (pinfunction "GND_4") (pintype "power_in"))
      (node (ref "FTDI_1") (pin "1") (pinfunction "1_1") (pintype "passive"))
      (node (ref "GND-") (pin "1") (pinfunction "1_1") (pintype "passive"))
      (node (ref "LED2") (pin "2") (pinfunction "2_2") (pintype "passive"))
      (node (ref "LED2") (pin "4") (pinfunction "4_4") (pintype "passive"))
      (node (ref "LED3") (pin "C") (pinfunction "C_C") (pintype "passive"))
      (node (ref "P17") (pin "1") (pinfunction "1_1") (pintype "passive"))
      (node (ref "P18") (pin "1") (pinfunction "1_1") (pintype "passive"))
      (node (ref "R1") (pin "2") (pinfunction "2_2") (pintype "passive"))
      (node (ref "R11") (pin "2") (pinfunction "2_2") (pintype "passive"))
      (node (ref "R3") (pin "2") (pinfunction "2_2") (pintype "passive"))
      (node (ref "R4") (pin "2") (pinfunction "2_2") (pintype "passive"))
      (node (ref "S1") (pin "3") (pinfunction "3_3") (pintype "passive"))
      (node (ref "S1") (pin "4") (pinfunction "4_4") (pintype "passive"))
      (node (ref "S2") (pin "4") (pinfunction "4_4") (pintype "passive"))
      (node (ref "U1") (pin "10") (pinfunction "VSS_10\\_10") (pintype "power_in"))
      (node (ref "U1") (pin "20") (pinfunction "VSSA_20") (pintype "power_in"))
      (node (ref "U1") (pin "27") (pinfunction "VSS_27_27") (pintype "power_in"))
      (node (ref "U1") (pin "74") (pinfunction "VSS_74_74") (pintype "power_in"))
      (node (ref "U1") (pin "99") (pinfunction "VSS_99_99") (pintype "power_in"))
      (node (ref "U2") (pin "23") (pinfunction "VSS_1_23") (pintype "power_in"))
      (node (ref "U2") (pin "35") (pinfunction "VSS_2_35") (pintype "power_in"))
      (node (ref "U2") (pin "44") (pinfunction "BOOT0_44") (pintype "bidirectional"))
      (node (ref "U2") (pin "47") (pinfunction "VSS_3_47") (pintype "power_in"))
      (node (ref "U2") (pin "8") (pinfunction "VSSA_8") (pintype "power_in"))
      (node (ref "U3") (pin "2") (pinfunction "GND_2") (pintype "power_in"))
      (node (ref "X1") (pin "GND") (pinfunction "GND_GND") (pintype "bidirectional"))
    )
    (net (code "70") (name "Net-(COINBATTERY-+)") (class "Default")
      (node (ref "COINBATTERY") (pin "PWR@2") (pinfunction "+_PWR@2") (pintype "power_in"))
      (node (ref "U1") (pin "6") (pinfunction "VBAT_6") (pintype "power_in"))
    )
    (net (code "71") (name "Net-(D2-A)") (class "Default")
      (node (ref "C11") (pin "1") (pinfunction "1_1") (pintype "passive"))
      (node (ref "D2") (pin "ANODE") (pinfunction "A_ANODE") (pintype "power_in"))
      (node (ref "U3") (pin "5") (pinfunction "VOUT_5") (pintype "power_in"))
    )
    (net (code "72") (name "Net-(LED2-Pad1)") (class "Default")
      (node (ref "LED2") (pin "1") (pinfunction "1_1") (pintype "passive"))
      (node (ref "RN2") (pin "5") (pinfunction "5_5") (pintype "passive"))
    )
    (net (code "73") (name "Net-(LED2-Pad3)") (class "Default")
      (node (ref "LED2") (pin "3") (pinfunction "3_3") (pintype "passive"))
      (node (ref "RN2") (pin "6") (pinfunction "6_6") (pintype "passive"))
    )
    (net (code "74") (name "Net-(LED3-PadA)") (class "Default")
      (node (ref "LED3") (pin "A") (pinfunction "A_A") (pintype "passive"))
      (node (ref "R5") (pin "1") (pinfunction "1_1") (pintype "passive"))
    )
    (net (code "75") (name "Net-(R9-Pad1)") (class "Default")
      (node (ref "R9") (pin "1") (pinfunction "1_1") (pintype "passive"))
      (node (ref "RN1") (pin "2") (pinfunction "2_2") (pintype "passive"))
      (node (ref "X1") (pin "D+") (pinfunction "D+_D+") (pintype "bidirectional"))
    )
    (net (code "76") (name "Net-(RN1-Pad1)") (class "Default")
      (node (ref "RN1") (pin "1") (pinfunction "1_1") (pintype "passive"))
      (node (ref "X1") (pin "D-") (pinfunction "D-_D-") (pintype "bidirectional"))
    )
    (net (code "77") (name "Net-(U1-PH0{slash}OSC_IN)") (class "Default")
      (node (ref "C6") (pin "1") (pinfunction "1_1") (pintype "passive"))
      (node (ref "U1") (pin "12") (pinfunction "PH0/OSC_IN_12") (pintype "bidirectional"))
      (node (ref "Y1") (pin "1") (pinfunction "P$1_1") (pintype "bidirectional"))
    )
    (net (code "78") (name "Net-(U1-PH1{slash}OSC_OUT)") (class "Default")
      (node (ref "C7") (pin "1") (pinfunction "1_1") (pintype "passive"))
      (node (ref "U1") (pin "13") (pinfunction "PH1/OSC_OUT_13") (pintype "bidirectional"))
      (node (ref "Y1") (pin "2") (pinfunction "P$2_2") (pintype "bidirectional"))
    )
    (net (code "79") (name "Net-(U1-VCAP_1)") (class "Default")
      (node (ref "C8") (pin "1") (pinfunction "1_1") (pintype "passive"))
      (node (ref "U1") (pin "49") (pinfunction "VCAP_1_49") (pintype "power_in"))
    )
    (net (code "80") (name "Net-(U1-VCAP_2)") (class "Default")
      (node (ref "C9") (pin "1") (pinfunction "1_1") (pintype "passive"))
      (node (ref "U1") (pin "73") (pinfunction "VCAP_2_73") (pintype "power_in"))
    )
    (net (code "81") (name "Net-(U2-PA8)") (class "Default")
      (node (ref "R9") (pin "2") (pinfunction "2_2") (pintype "passive"))
      (node (ref "U2") (pin "29") (pinfunction "PA8_29") (pintype "bidirectional"))
    )
    (net (code "82") (name "Net-(U2-PA11_USB_DM)") (class "Default")
      (node (ref "RN1") (pin "4") (pinfunction "4_4") (pintype "passive"))
      (node (ref "U2") (pin "32") (pinfunction "PA11_USB_DM_32") (pintype "bidirectional"))
    )
    (net (code "83") (name "Net-(U2-PA12_USB_DP)") (class "Default")
      (node (ref "RN1") (pin "3") (pinfunction "3_3") (pintype "passive"))
      (node (ref "U2") (pin "33") (pinfunction "PA12_USB_DP_33") (pintype "bidirectional"))
    )
    (net (code "84") (name "Net-(U2-PB12)") (class "Default")
      (node (ref "R14") (pin "2") (pinfunction "2_2") (pintype "passive"))
      (node (ref "S1") (pin "2") (pinfunction "2_2") (pintype "passive"))
      (node (ref "U2") (pin "25") (pinfunction "PB12_25") (pintype "bidirectional"))
    )
    (net (code "85") (name "Net-(U2-PD0_OSC_IN)") (class "Default")
      (node (ref "C17") (pin "1") (pinfunction "1_1") (pintype "passive"))
      (node (ref "U2") (pin "5") (pinfunction "PD0_OSC_IN_5") (pintype "bidirectional"))
      (node (ref "Y2") (pin "1") (pinfunction "P$1_1") (pintype "bidirectional"))
    )
    (net (code "86") (name "Net-(U2-PD1_OSC_OUT)") (class "Default")
      (node (ref "C18") (pin "1") (pinfunction "1_1") (pintype "passive"))
      (node (ref "U2") (pin "6") (pinfunction "PD1_OSC_OUT_6") (pintype "bidirectional"))
      (node (ref "Y2") (pin "2") (pinfunction "P$2_2") (pintype "bidirectional"))
    )
    (net (code "87") (name "unconnected-(FTDI_2-Pad1)") (class "Default")
      (node (ref "FTDI_2") (pin "1") (pinfunction "1_1") (pintype "passive"))
    )
    (net (code "88") (name "unconnected-(FTDI_3-Pad1)") (class "Default")
      (node (ref "FTDI_3") (pin "1") (pinfunction "1_1") (pintype "passive"))
    )
    (net (code "89") (name "unconnected-(FTDI_6-Pad1)") (class "Default")
      (node (ref "FTDI_6") (pin "1") (pinfunction "1_1") (pintype "passive"))
    )
    (net (code "90") (name "unconnected-(RN2-Pad1)") (class "Default")
      (node (ref "RN2") (pin "1") (pinfunction "1_1") (pintype "passive"))
    )
    (net (code "91") (name "unconnected-(RN2-Pad2)") (class "Default")
      (node (ref "RN2") (pin "2") (pinfunction "2_2") (pintype "passive"))
    )
    (net (code "92") (name "unconnected-(RN2-Pad7)") (class "Default")
      (node (ref "RN2") (pin "7") (pinfunction "7_7") (pintype "passive"))
    )
    (net (code "93") (name "unconnected-(RN2-Pad8)") (class "Default")
      (node (ref "RN2") (pin "8") (pinfunction "8_8") (pintype "passive"))
    )
    (net (code "94") (name "unconnected-(S1-Pad1)") (class "Default")
      (node (ref "S1") (pin "1") (pinfunction "1_1") (pintype "passive"))
    )
    (net (code "95") (name "unconnected-(S2-Pad1)") (class "Default")
      (node (ref "S2") (pin "1") (pinfunction "1_1") (pintype "passive"))
    )
    (net (code "96") (name "unconnected-(S2-Pad3)") (class "Default")
      (node (ref "S2") (pin "3") (pinfunction "3_3") (pintype "passive"))
    )
    (net (code "97") (name "unconnected-(U1-PD0{slash}CAN1_RX-Pad81)") (class "Default")
      (node (ref "U1") (pin "81") (pinfunction "PD0/CAN1_RX_81") (pintype "bidirectional"))
    )
    (net (code "98") (name "unconnected-(U1-PD1{slash}CAN1_TX-Pad82)") (class "Default")
      (node (ref "U1") (pin "82") (pinfunction "PD1/CAN1_TX_82") (pintype "bidirectional"))
    )
    (net (code "99") (name "unconnected-(U1-PD3{slash}USART2_CTS-Pad84)") (class "Default")
      (node (ref "U1") (pin "84") (pinfunction "PD3/USART2_CTS_84") (pintype "bidirectional"))
    )
    (net (code "100") (name "unconnected-(U1-PD4{slash}USART2_RTS-Pad85)") (class "Default")
      (node (ref "U1") (pin "85") (pinfunction "PD4/USART2_RTS_85") (pintype "bidirectional"))
    )
    (net (code "101") (name "unconnected-(U1-PD7{slash}USART2_CK-Pad88)") (class "Default")
      (node (ref "U1") (pin "88") (pinfunction "PD7/USART2_CK_88") (pintype "bidirectional"))
    )
    (net (code "102") (name "unconnected-(U1-PD8{slash}USART3_TX-Pad55)") (class "Default")
      (node (ref "U1") (pin "55") (pinfunction "PD8/USART3_TX_55") (pintype "bidirectional"))
    )
    (net (code "103") (name "unconnected-(U1-PD9{slash}USART3_RX-Pad56)") (class "Default")
      (node (ref "U1") (pin "56") (pinfunction "PD9/USART3_RX_56") (pintype "bidirectional"))
    )
    (net (code "104") (name "unconnected-(U1-PD10{slash}USART3_CK-Pad57)") (class "Default")
      (node (ref "U1") (pin "57") (pinfunction "PD10/USART3_CK_57") (pintype "bidirectional"))
    )
    (net (code "105") (name "unconnected-(U1-PD11{slash}USART3_CTS-Pad58)") (class "Default")
      (node (ref "U1") (pin "58") (pinfunction "PD11/USART3_CTS_58") (pintype "bidirectional"))
    )
    (net (code "106") (name "unconnected-(U1-PD12{slash}TIM4_CH1{slash}USART3_RTS-Pad59)") (class "Default")
      (node (ref "U1") (pin "59") (pinfunction "PD12/TIM4_CH1/USART3_RTS_59") (pintype "bidirectional"))
    )
    (net (code "107") (name "unconnected-(U1-PD13{slash}TIM4_CH2-Pad60)") (class "Default")
      (node (ref "U1") (pin "60") (pinfunction "PD13/TIM4_CH2_60") (pintype "bidirectional"))
    )
    (net (code "108") (name "unconnected-(U1-PD14{slash}TIM4_CH3-Pad61)") (class "Default")
      (node (ref "U1") (pin "61") (pinfunction "PD14/TIM4_CH3_61") (pintype "bidirectional"))
    )
    (net (code "109") (name "unconnected-(U1-PD15{slash}TIM4_CH4-Pad62)") (class "Default")
      (node (ref "U1") (pin "62") (pinfunction "PD15/TIM4_CH4_62") (pintype "bidirectional"))
    )
    (net (code "110") (name "unconnected-(U1-PE0{slash}TIM4_ETR-Pad97)") (class "Default")
      (node (ref "U1") (pin "97") (pinfunction "PE0/TIM4_ETR_97") (pintype "bidirectional"))
    )
    (net (code "111") (name "unconnected-(U1-PE1-Pad98)") (class "Default")
      (node (ref "U1") (pin "98") (pinfunction "PE1_98") (pintype "bidirectional"))
    )
    (net (code "112") (name "unconnected-(U1-PE2{slash}TRACECLK-Pad1)") (class "Default")
      (node (ref "U1") (pin "1") (pinfunction "PE2/TRACECLK_1") (pintype "bidirectional"))
    )
    (net (code "113") (name "unconnected-(U1-PE3{slash}TRACED0-Pad2)") (class "Default")
      (node (ref "U1") (pin "2") (pinfunction "PE3/TRACED0_2") (pintype "bidirectional"))
    )
    (net (code "114") (name "unconnected-(U1-PE4{slash}TRACED1-Pad3)") (class "Default")
      (node (ref "U1") (pin "3") (pinfunction "PE4/TRACED1_3") (pintype "bidirectional"))
    )
    (net (code "115") (name "unconnected-(U1-PE5{slash}TRACED2{slash}TIM9_CH1-Pad4)") (class "Default")
      (node (ref "U1") (pin "4") (pinfunction "PE5/TRACED2/TIM9_CH1_4") (pintype "bidirectional"))
    )
    (net (code "116") (name "unconnected-(U1-PE6{slash}TRACED3{slash}TIM9_CH2-Pad5)") (class "Default")
      (node (ref "U1") (pin "5") (pinfunction "PE6/TRACED3/TIM9_CH2_5") (pintype "bidirectional"))
    )
    (net (code "117") (name "unconnected-(U1-PE7{slash}TIM1_ETR-Pad38)") (class "Default")
      (node (ref "U1") (pin "38") (pinfunction "PE7/TIM1_ETR_38") (pintype "bidirectional"))
    )
    (net (code "118") (name "unconnected-(U1-PE8{slash}TIM1_CH1N-Pad39)") (class "Default")
      (node (ref "U1") (pin "39") (pinfunction "PE8/TIM1_CH1N_39") (pintype "bidirectional"))
    )
    (net (code "119") (name "unconnected-(U1-PE9{slash}TIM1_CH1-Pad40)") (class "Default")
      (node (ref "U1") (pin "40") (pinfunction "PE9/TIM1_CH1_40") (pintype "bidirectional"))
    )
    (net (code "120") (name "unconnected-(U1-PE10{slash}TIM1_CH2N-Pad41)") (class "Default")
      (node (ref "U1") (pin "41") (pinfunction "PE10/TIM1_CH2N_41") (pintype "bidirectional"))
    )
    (net (code "121") (name "unconnected-(U1-PE11{slash}TIM1_CH2-Pad42)") (class "Default")
      (node (ref "U1") (pin "42") (pinfunction "PE11/TIM1_CH2_42") (pintype "bidirectional"))
    )
    (net (code "122") (name "unconnected-(U1-PE12{slash}TIM1_CH3N-Pad43)") (class "Default")
      (node (ref "U1") (pin "43") (pinfunction "PE12/TIM1_CH3N_43") (pintype "bidirectional"))
    )
    (net (code "123") (name "unconnected-(U1-PE13{slash}TIM1_CH3-Pad44)") (class "Default")
      (node (ref "U1") (pin "44") (pinfunction "PE13/TIM1_CH3_44") (pintype "bidirectional"))
    )
    (net (code "124") (name "unconnected-(U1-PE14{slash}TIM1_CH4-Pad45)") (class "Default")
      (node (ref "U1") (pin "45") (pinfunction "PE14/TIM1_CH4_45") (pintype "bidirectional"))
    )
    (net (code "125") (name "unconnected-(U1-PE15{slash}TIM1_BKIN-Pad46)") (class "Default")
      (node (ref "U1") (pin "46") (pinfunction "PE15/TIM1_BKIN_46") (pintype "bidirectional"))
    )
    (net (code "126") (name "unconnected-(U2-PA0-Pad10)") (class "Default")
      (node (ref "U2") (pin "10") (pinfunction "PA0_10") (pintype "bidirectional"))
    )
    (net (code "127") (name "unconnected-(U2-PA1-Pad11)") (class "Default")
      (node (ref "U2") (pin "11") (pinfunction "PA1_11") (pintype "bidirectional"))
    )
    (net (code "128") (name "unconnected-(U2-PA7-Pad17)") (class "Default")
      (node (ref "U2") (pin "17") (pinfunction "PA7_17") (pintype "bidirectional"))
    )
    (net (code "129") (name "unconnected-(U2-PA9_UART1_TX-Pad30)") (class "Default")
      (node (ref "U2") (pin "30") (pinfunction "PA9_UART1_TX_30") (pintype "bidirectional"))
    )
    (net (code "130") (name "unconnected-(U2-PA10_UART1_RX-Pad31)") (class "Default")
      (node (ref "U2") (pin "31") (pinfunction "PA10_UART1_RX_31") (pintype "bidirectional"))
    )
    (net (code "131") (name "unconnected-(U2-PA15_JTDI-Pad38)") (class "Default")
      (node (ref "U2") (pin "38") (pinfunction "PA15_JTDI_38") (pintype "bidirectional"))
    )
    (net (code "132") (name "unconnected-(U2-PB6-Pad42)") (class "Default")
      (node (ref "U2") (pin "42") (pinfunction "PB6_42") (pintype "bidirectional"))
    )
    (net (code "133") (name "unconnected-(U2-PB7-Pad43)") (class "Default")
      (node (ref "U2") (pin "43") (pinfunction "PB7_43") (pintype "bidirectional"))
    )
    (net (code "134") (name "unconnected-(U2-PB8-Pad45)") (class "Default")
      (node (ref "U2") (pin "45") (pinfunction "PB8_45") (pintype "bidirectional"))
    )
    (net (code "135") (name "unconnected-(U2-PB9-Pad46)") (class "Default")
      (node (ref "U2") (pin "46") (pinfunction "PB9_46") (pintype "bidirectional"))
    )
    (net (code "136") (name "unconnected-(U2-PB14-Pad27)") (class "Default")
      (node (ref "U2") (pin "27") (pinfunction "PB14_27") (pintype "bidirectional"))
    )
    (net (code "137") (name "unconnected-(U2-PB15-Pad28)") (class "Default")
      (node (ref "U2") (pin "28") (pinfunction "PB15_28") (pintype "bidirectional"))
    )
    (net (code "138") (name "unconnected-(U2-PC13-Pad2)") (class "Default")
      (node (ref "U2") (pin "2") (pinfunction "PC13_2") (pintype "bidirectional"))
    )
    (net (code "139") (name "unconnected-(U2-PC14-Pad3)") (class "Default")
      (node (ref "U2") (pin "3") (pinfunction "PC14_3") (pintype "bidirectional"))
    )
    (net (code "140") (name "unconnected-(U2-PC15-Pad4)") (class "Default")
      (node (ref "U2") (pin "4") (pinfunction "PC15_4") (pintype "bidirectional"))
    )
    (net (code "141") (name "unconnected-(U3-NC-Pad4)") (class "Default")
      (node (ref "U3") (pin "4") (pinfunction "NC_4") (pintype "no_connect"))
    )
  )
)
